# AFE_mezzanine.net
KiCad netlist of a schematic drawn in Altium Designer
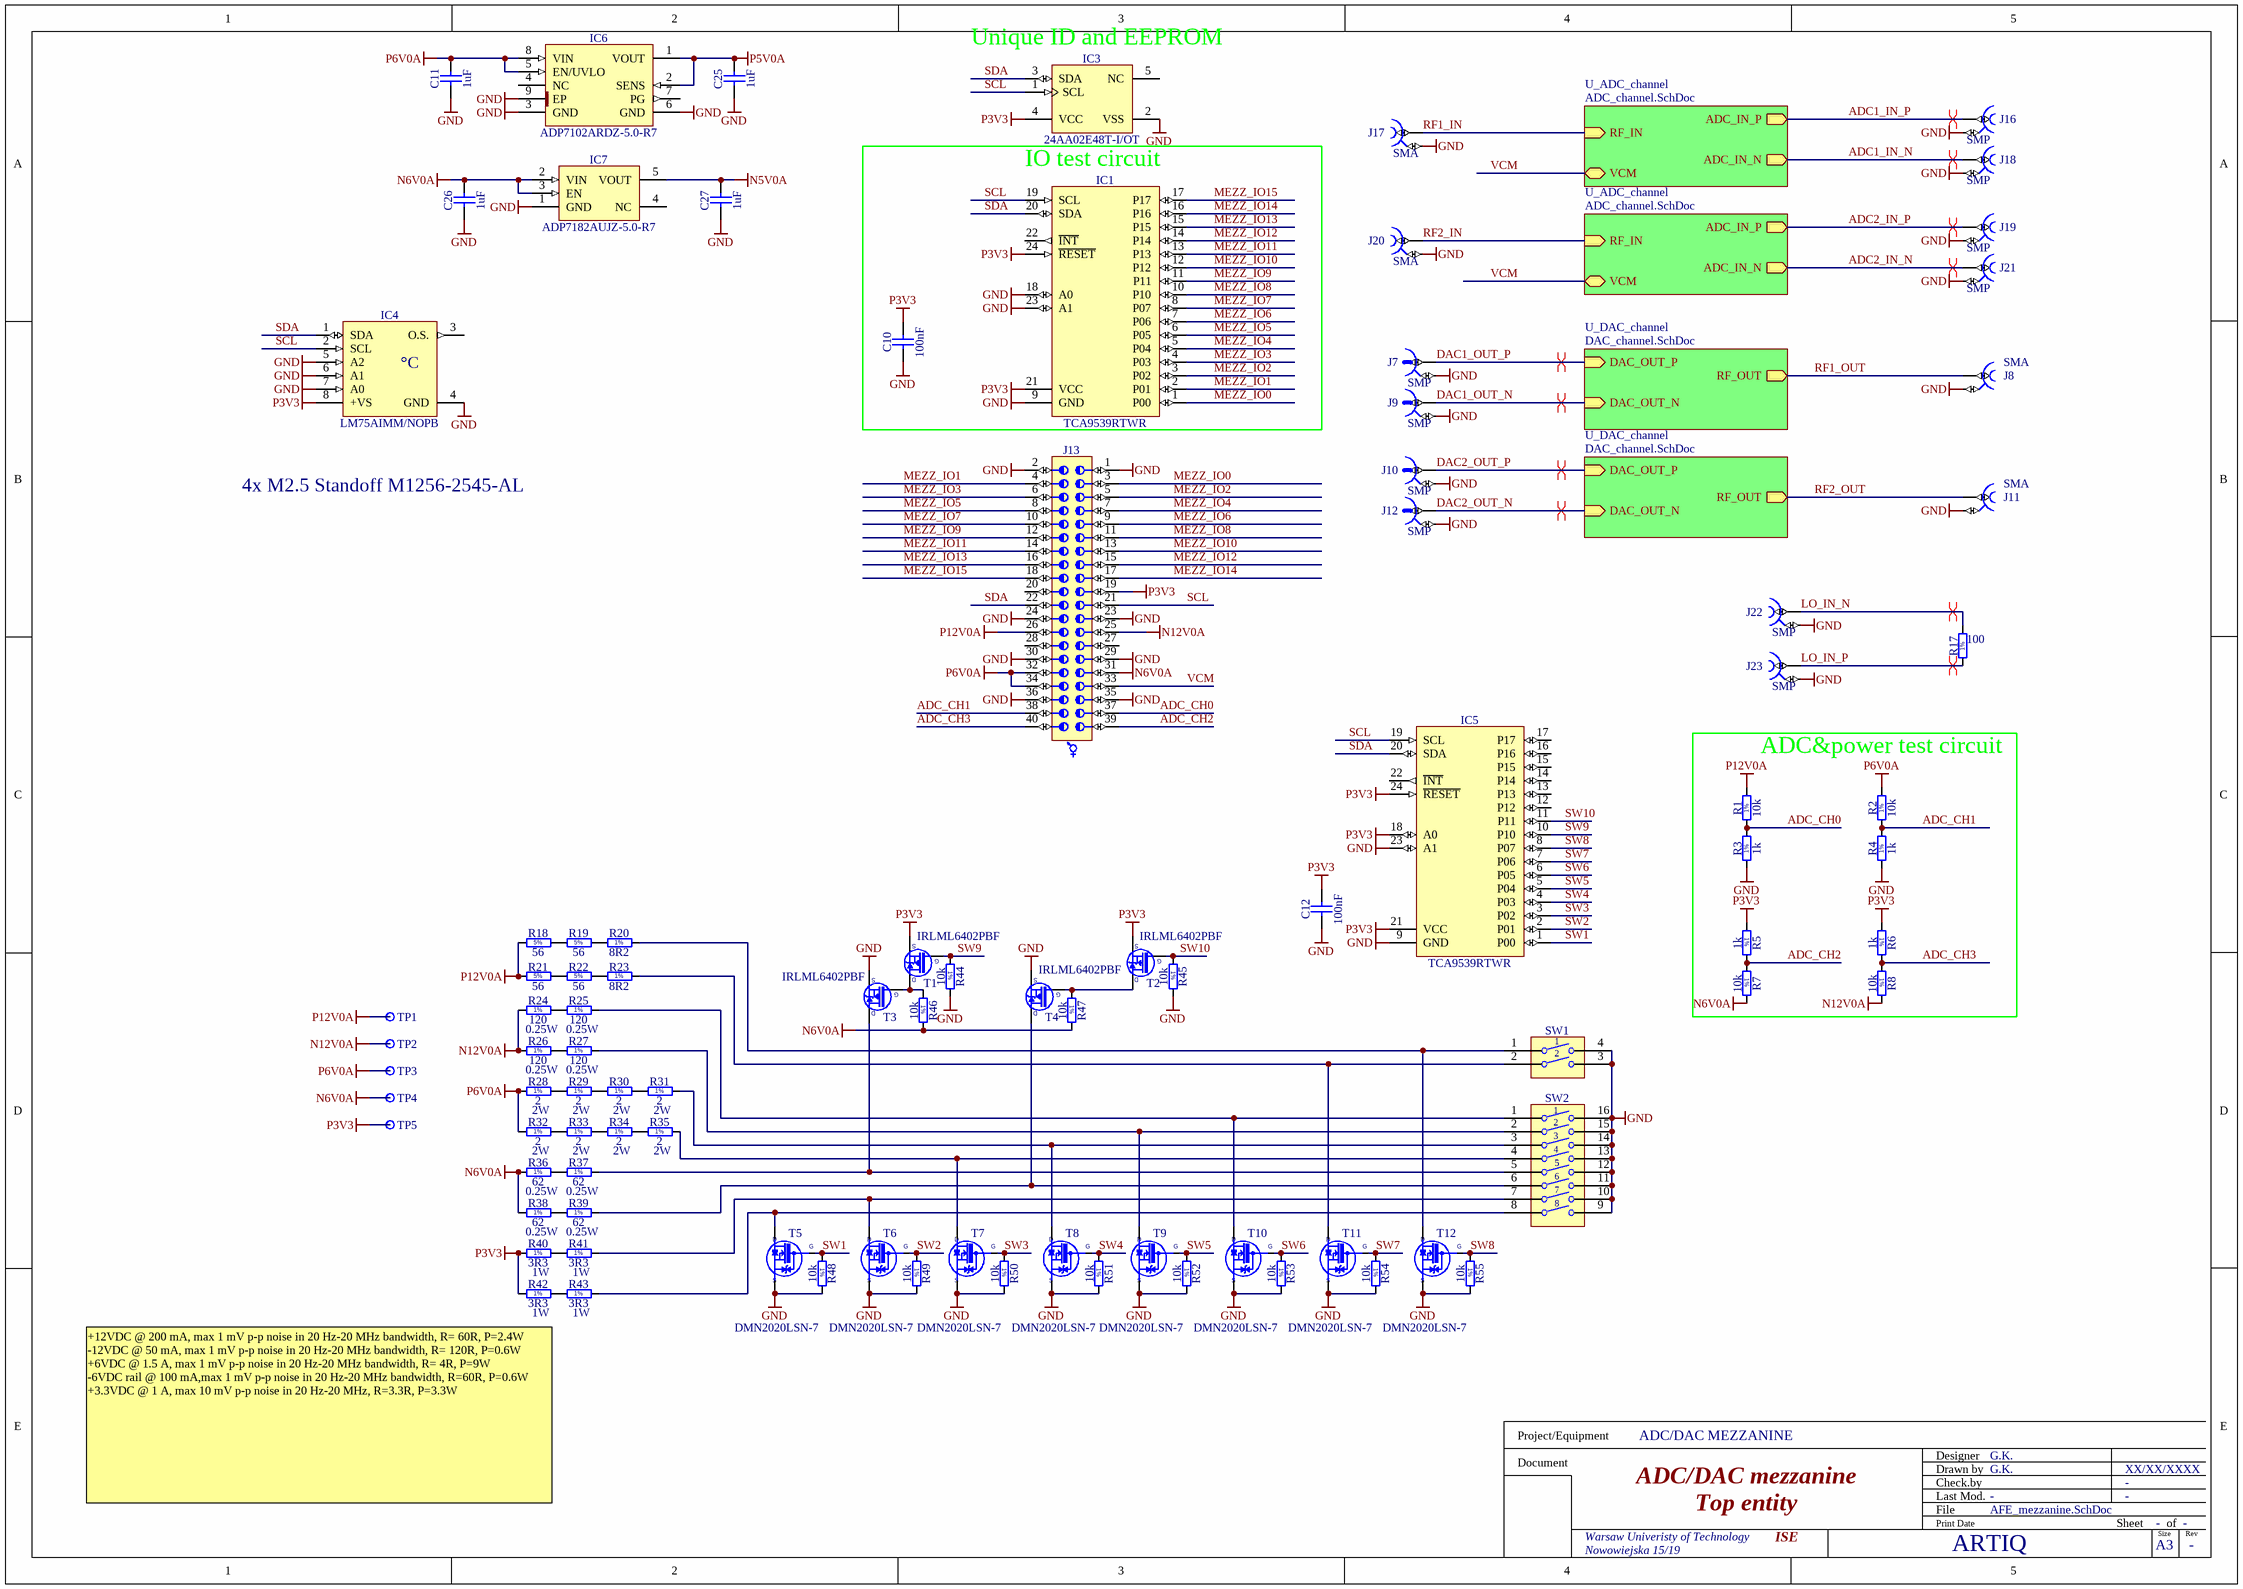
[diagram p0: AFE_mezzanine.SchDoc]

(export (version "E")
  (design (tool "Eeschema 10.0.6"))
  (components
    (comp (ref "C10")
      (value "100nF")
      (footprint "CAPC1005X55N")
      (description "Non-polarised capacitor")
      (fields
        (field (name "PART NUMBER") "CC0402_100NF_16V_10%_X5R")
        (field (name "VOLTAGE") "16V")
        (field (name "AUTHOR") "CERN DEM JLC")
      )
      (libsource (lib "Capacitors") (part "Capacitor - non polarized"))
    )
    (comp (ref "C11")
      (value "1uF")
      (footprint "CAPC2012X140N")
      (description "Non-polarised capacitor")
      (fields
        (field (name "PART NUMBER") "CC0805_1UF_35V_20%_X7R")
        (field (name "VOLTAGE") "35V")
        (field (name "AUTHOR") "CERN DEM JLC")
      )
      (libsource (lib "Capacitors") (part "Capacitor - non polarized"))
    )
    (comp (ref "C12")
      (value "100nF")
      (footprint "CAPC1005X55N")
      (description "Non-polarised capacitor")
      (fields
        (field (name "PART NUMBER") "CC0402_100NF_16V_10%_X5R")
        (field (name "VOLTAGE") "16V")
        (field (name "AUTHOR") "CERN DEM JLC")
      )
      (libsource (lib "Capacitors") (part "Capacitor - non polarized"))
    )
    (comp (ref "C25")
      (value "1uF")
      (footprint "CAPC2012X140N")
      (description "Non-polarised capacitor")
      (fields
        (field (name "PART NUMBER") "CC0805_1UF_35V_20%_X7R")
        (field (name "VOLTAGE") "35V")
        (field (name "AUTHOR") "CERN DEM JLC")
      )
      (libsource (lib "Capacitors") (part "Capacitor - non polarized"))
    )
    (comp (ref "C26")
      (value "1uF")
      (footprint "CAPC2012X140N")
      (description "Non-polarised capacitor")
      (fields
        (field (name "PART NUMBER") "CC0805_1UF_35V_20%_X7R")
        (field (name "VOLTAGE") "35V")
        (field (name "AUTHOR") "CERN DEM JLC")
      )
      (libsource (lib "Capacitors") (part "Capacitor - non polarized"))
    )
    (comp (ref "C27")
      (value "1uF")
      (footprint "CAPC2012X140N")
      (description "Non-polarised capacitor")
      (fields
        (field (name "PART NUMBER") "CC0805_1UF_35V_20%_X7R")
        (field (name "VOLTAGE") "35V")
        (field (name "AUTHOR") "CERN DEM JLC")
      )
      (libsource (lib "Capacitors") (part "Capacitor - non polarized"))
    )
    (comp (ref "IC1")
      (value "TCA9539RTWR")
      (footprint "QFN50P400X400X80-25N-S255")
      (description "Low-Voltage 16-Bit I2C and SMBus I/O Expander")
      (fields (field (name "MANUFACTURER") "TEXAS INSTRUMENTS") (field (name "AUTHOR") "CERN DEM MR"))
      (libsource (lib "ICs And Semiconductors") (part "TCA9539RTWR"))
    )
    (comp (ref "IC3")
      (value "24AA02E48T-I/OT")
      (footprint "SOT95P280X145-5N")
      (description "1.7V-5.5V, 2K I2C Serial EEPROM With EUI-48 Node Identity")
      (fields (field (name "MANUFACTURER") "MICROCHIP TECHNOLOGY") (field (name "AUTHOR") "CERN DEM MR"))
      (libsource (lib "ICs And Semiconductors") (part "24AA02E48T-I/OT"))
    )
    (comp (ref "IC4")
      (value "LM75AIMM/NOPB")
      (footprint "SOP65P490X109-8N")
      (description "Digital Temperature Sensor and Thermal Watchdog with Two-Wire Interface")
      (fields (field (name "MANUFACTURER") "TEXAS INSTRUMENTS") (field (name "AUTHOR") "CERN DEM JLC"))
      (libsource (lib "ICs And Semiconductors") (part "LM75"))
    )
    (comp (ref "IC5")
      (value "TCA9539RTWR")
      (footprint "QFN50P400X400X80-25N-S255")
      (description "Low-Voltage 16-Bit I2C and SMBus I/O Expander")
      (fields (field (name "MANUFACTURER") "TEXAS INSTRUMENTS") (field (name "AUTHOR") "CERN DEM MR"))
      (libsource (lib "ICs And Semiconductors") (part "TCA9539RTWR"))
    )
    (comp (ref "IC6")
      (value "ADP7102ARDZ-5.0-R7")
      (footprint "SOIC127P600X175-9N-R241X309")
      (description "300 mA, Low Noise, CMOS LDO Linear Regulator")
      (fields (field (name "MANUFACTURER") "ANALOG DEVICES") (field (name "AUTHOR") "CERN DEM JLC"))
      (libsource (lib "ICs And Semiconductors") (part "ADP7102ARDZ-X.X-R7"))
    )
    (comp (ref "IC7")
      (value "ADP7182AUJZ-5.0-R7")
      (footprint "SOT95P280X90-5N")
      (description "–5V, 200 mA, Low Noise, Linear Regulator")
      (fields (field (name "MANUFACTURER") "ANALOG DEVICES") (field (name "AUTHOR") "CERN DEM JLC"))
      (libsource (lib "ICs And Semiconductors") (part "ADP7182AUJZ-X.X-R7"))
    )
    (comp (ref "J7")
      (value "SMP")
      (footprint "MOLEX_85305-0232")
      (fields
        (field (name "PART NUMBER") "MOLEX_85305-0232")
        (field (name "MANUFACTURER") "MOLEX")
        (field (name "MANUFACTURER PART NUMBER") "85305-0232")
        (field (name "AUTHOR") "CERN DEM JMW")
      )
      (libsource (lib "Connectors") (part "Coax_1Male_1Shield"))
    )
    (comp (ref "J8")
      (value "SMA")
      (footprint "TELEGARTNER_J01151A0451")
      (fields
        (field (name "PART NUMBER") "TELEGARTNER_J01151A0451")
        (field (name "MANUFACTURER") "TELEGARTNER")
        (field (name "MANUFACTURER PART NUMBER") "J01151A0451")
        (field (name "AUTHOR") "CERN DEM JLC")
      )
      (libsource (lib "") (part "Coax_1Female_1Shield_1"))
    )
    (comp (ref "J9")
      (value "SMP")
      (footprint "MOLEX_85305-0232")
      (fields
        (field (name "PART NUMBER") "MOLEX_85305-0232")
        (field (name "MANUFACTURER") "MOLEX")
        (field (name "MANUFACTURER PART NUMBER") "85305-0232")
        (field (name "AUTHOR") "CERN DEM JMW")
      )
      (libsource (lib "Connectors") (part "Coax_1Male_1Shield"))
    )
    (comp (ref "J10")
      (value "SMP")
      (footprint "MOLEX_85305-0232")
      (fields
        (field (name "PART NUMBER") "MOLEX_85305-0232")
        (field (name "MANUFACTURER") "MOLEX")
        (field (name "MANUFACTURER PART NUMBER") "85305-0232")
        (field (name "AUTHOR") "CERN DEM JMW")
      )
      (libsource (lib "Connectors") (part "Coax_1Male_1Shield"))
    )
    (comp (ref "J11")
      (value "SMA")
      (footprint "TELEGARTNER_J01151A0451")
      (fields
        (field (name "PART NUMBER") "TELEGARTNER_J01151A0451")
        (field (name "MANUFACTURER") "TELEGARTNER")
        (field (name "MANUFACTURER PART NUMBER") "J01151A0451")
        (field (name "AUTHOR") "CERN DEM JLC")
      )
      (libsource (lib "") (part "Coax_1Female_1Shield_1"))
    )
    (comp (ref "J12")
      (value "SMP")
      (footprint "MOLEX_85305-0232")
      (fields
        (field (name "PART NUMBER") "MOLEX_85305-0232")
        (field (name "MANUFACTURER") "MOLEX")
        (field (name "MANUFACTURER PART NUMBER") "85305-0232")
        (field (name "AUTHOR") "CERN DEM JMW")
      )
      (libsource (lib "Connectors") (part "Coax_1Male_1Shield"))
    )
    (comp (ref "J13")
      (value "~")
      (footprint "SAMTEC_LSS-120-03-L-DV-A")
      (description "Connector 40 Hermaphroditic")
      (fields
        (field (name "PART NUMBER") "SAMTEC_LSS-120-03-L-DV-A")
        (field (name "MANUFACTURER") "SAMTEC")
        (field (name "AUTHOR") "CERN DEM JMW")
      )
      (libsource (lib "Connectors") (part "Connector 40 Hermaphroditic"))
    )
    (comp (ref "J16")
      (value "SMP")
      (footprint "AMPHENOL_SMP-MSLD-PCT-10")
      (fields
        (field (name "PART NUMBER") "AMPHENOL_SMP-MSLD-PCT-10")
        (field (name "MANUFACTURER") "AMPHENOL")
        (field (name "MANUFACTURER PART NUMBER") "SMP-MSLD-PCT-10")
        (field (name "AUTHOR") "CERN DEM JLC")
      )
      (libsource (lib "") (part "Coax_1Female_1Shield_1"))
    )
    (comp (ref "J17")
      (value "SMA")
      (footprint "TELEGARTNER_J01151A0921")
      (fields
        (field (name "PART NUMBER") "TELEGARTNER_J01151A0921")
        (field (name "MANUFACTURER") "TELEGARTNER")
        (field (name "MANUFACTURER PART NUMBER") "J01151A0921")
        (field (name "AUTHOR") "CERN DEM JLC")
      )
      (libsource (lib "Connectors") (part "Coax_1Female_1Shield"))
    )
    (comp (ref "J18")
      (value "SMP")
      (footprint "AMPHENOL_SMP-MSLD-PCT-10")
      (fields
        (field (name "PART NUMBER") "AMPHENOL_SMP-MSLD-PCT-10")
        (field (name "MANUFACTURER") "AMPHENOL")
        (field (name "MANUFACTURER PART NUMBER") "SMP-MSLD-PCT-10")
        (field (name "AUTHOR") "CERN DEM JLC")
      )
      (libsource (lib "") (part "Coax_1Female_1Shield_1"))
    )
    (comp (ref "J19")
      (value "SMP")
      (footprint "AMPHENOL_SMP-MSLD-PCT-10")
      (fields
        (field (name "PART NUMBER") "AMPHENOL_SMP-MSLD-PCT-10")
        (field (name "MANUFACTURER") "AMPHENOL")
        (field (name "MANUFACTURER PART NUMBER") "SMP-MSLD-PCT-10")
        (field (name "AUTHOR") "CERN DEM JLC")
      )
      (libsource (lib "") (part "Coax_1Female_1Shield_1"))
    )
    (comp (ref "J20")
      (value "SMA")
      (footprint "TELEGARTNER_J01151A0921")
      (fields
        (field (name "PART NUMBER") "TELEGARTNER_J01151A0921")
        (field (name "MANUFACTURER") "TELEGARTNER")
        (field (name "MANUFACTURER PART NUMBER") "J01151A0921")
        (field (name "AUTHOR") "CERN DEM JLC")
      )
      (libsource (lib "Connectors") (part "Coax_1Female_1Shield"))
    )
    (comp (ref "J21")
      (value "SMP")
      (footprint "AMPHENOL_SMP-MSLD-PCT-10")
      (fields
        (field (name "PART NUMBER") "AMPHENOL_SMP-MSLD-PCT-10")
        (field (name "MANUFACTURER") "AMPHENOL")
        (field (name "MANUFACTURER PART NUMBER") "SMP-MSLD-PCT-10")
        (field (name "AUTHOR") "CERN DEM JLC")
      )
      (libsource (lib "") (part "Coax_1Female_1Shield_1"))
    )
    (comp (ref "J22")
      (value "SMP")
      (footprint "AMPHENOL_SMP-MSLD-PCT-10")
      (fields
        (field (name "PART NUMBER") "AMPHENOL_SMP-MSLD-PCT-10")
        (field (name "MANUFACTURER") "AMPHENOL")
        (field (name "MANUFACTURER PART NUMBER") "SMP-MSLD-PCT-10")
        (field (name "AUTHOR") "CERN DEM JLC")
      )
      (libsource (lib "Connectors") (part "Coax_1Female_1Shield"))
    )
    (comp (ref "J23")
      (value "SMP")
      (footprint "AMPHENOL_SMP-MSLD-PCT-10")
      (fields
        (field (name "PART NUMBER") "AMPHENOL_SMP-MSLD-PCT-10")
        (field (name "MANUFACTURER") "AMPHENOL")
        (field (name "MANUFACTURER PART NUMBER") "SMP-MSLD-PCT-10")
        (field (name "AUTHOR") "CERN DEM JLC")
      )
      (libsource (lib "Connectors") (part "Coax_1Female_1Shield"))
    )
    (comp (ref "R1")
      (value "10k")
      (footprint "RESC1005X40N")
      (description "Resistor - 1%")
      (fields
        (field (name "PART NUMBER") "R0402_10K_1%_0.0625W_100PPM")
        (field (name "POWER") "0.0625W")
        (field (name "AUTHOR") "CERN DEM JLC")
      )
      (libsource (lib "Resistors") (part "Resistor - 1%"))
    )
    (comp (ref "R2")
      (value "10k")
      (footprint "RESC1005X40N")
      (description "Resistor - 1%")
      (fields
        (field (name "PART NUMBER") "R0402_10K_1%_0.0625W_100PPM")
        (field (name "POWER") "0.0625W")
        (field (name "AUTHOR") "CERN DEM JLC")
      )
      (libsource (lib "Resistors") (part "Resistor - 1%"))
    )
    (comp (ref "R3")
      (value "1k")
      (footprint "RESC1005X40N")
      (description "Resistor - 1%")
      (fields
        (field (name "PART NUMBER") "R0402_1K_1%_0.0625W_100PPM")
        (field (name "POWER") "0.0625W")
        (field (name "AUTHOR") "CERN DEM JLC")
      )
      (libsource (lib "Resistors") (part "Resistor - 1%"))
    )
    (comp (ref "R4")
      (value "1k")
      (footprint "RESC1005X40N")
      (description "Resistor - 1%")
      (fields
        (field (name "PART NUMBER") "R0402_1K_1%_0.0625W_100PPM")
        (field (name "POWER") "0.0625W")
        (field (name "AUTHOR") "CERN DEM JLC")
      )
      (libsource (lib "Resistors") (part "Resistor - 1%"))
    )
    (comp (ref "R5")
      (value "1k")
      (footprint "RESC1005X40N")
      (description "Resistor - 1%")
      (fields
        (field (name "PART NUMBER") "R0402_1K_1%_0.0625W_100PPM")
        (field (name "POWER") "0.0625W")
        (field (name "AUTHOR") "CERN DEM JLC")
      )
      (libsource (lib "Resistors") (part "Resistor - 1%"))
    )
    (comp (ref "R6")
      (value "1k")
      (footprint "RESC1005X40N")
      (description "Resistor - 1%")
      (fields
        (field (name "PART NUMBER") "R0402_1K_1%_0.0625W_100PPM")
        (field (name "POWER") "0.0625W")
        (field (name "AUTHOR") "CERN DEM JLC")
      )
      (libsource (lib "Resistors") (part "Resistor - 1%"))
    )
    (comp (ref "R7")
      (value "10k")
      (footprint "RESC1005X40N")
      (description "Resistor - 1%")
      (fields
        (field (name "PART NUMBER") "R0402_10K_1%_0.0625W_100PPM")
        (field (name "POWER") "0.0625W")
        (field (name "AUTHOR") "CERN DEM JLC")
      )
      (libsource (lib "Resistors") (part "Resistor - 1%"))
    )
    (comp (ref "R8")
      (value "10k")
      (footprint "RESC1005X40N")
      (description "Resistor - 1%")
      (fields
        (field (name "PART NUMBER") "R0402_10K_1%_0.0625W_100PPM")
        (field (name "POWER") "0.0625W")
        (field (name "AUTHOR") "CERN DEM JLC")
      )
      (libsource (lib "Resistors") (part "Resistor - 1%"))
    )
    (comp (ref "R17")
      (value "100")
      (footprint "RESC1005X40N")
      (description "Resistor - 1%")
      (fields
        (field (name "PART NUMBER") "R0402_100R_1%_0.0625W_100PPM")
        (field (name "POWER") "0.0625W")
        (field (name "AUTHOR") "CERN DEM JLC")
      )
      (libsource (lib "Resistors") (part "Resistor - 1%"))
    )
    (comp (ref "R18")
      (value "56")
      (footprint "RESC6331X70N")
      (description "Resistor - 5%")
      (fields
        (field (name "PART NUMBER") "R2512_56R_5%_1W_200PPM")
        (field (name "POWER") "1W")
        (field (name "AUTHOR") "CERN DEM JLC")
      )
      (libsource (lib "Resistors") (part "Resistor - 5%"))
    )
    (comp (ref "R19")
      (value "56")
      (footprint "RESC6331X70N")
      (description "Resistor - 5%")
      (fields
        (field (name "PART NUMBER") "R2512_56R_5%_1W_200PPM")
        (field (name "POWER") "1W")
        (field (name "AUTHOR") "CERN DEM JLC")
      )
      (libsource (lib "Resistors") (part "Resistor - 5%"))
    )
    (comp (ref "R20")
      (value "8R2")
      (footprint "RESC3216X65N")
      (description "Resistor - 1%")
      (fields
        (field (name "PART NUMBER") "R1206_8R2_1%_0.25W_200PPM")
        (field (name "POWER") "0.25W")
        (field (name "AUTHOR") "CERN DEM JLC")
      )
      (libsource (lib "Resistors") (part "Resistor - 1%"))
    )
    (comp (ref "R21")
      (value "56")
      (footprint "RESC6331X70N")
      (description "Resistor - 5%")
      (fields
        (field (name "PART NUMBER") "R2512_56R_5%_1W_200PPM")
        (field (name "POWER") "1W")
        (field (name "AUTHOR") "CERN DEM JLC")
      )
      (libsource (lib "Resistors") (part "Resistor - 5%"))
    )
    (comp (ref "R22")
      (value "56")
      (footprint "RESC6331X70N")
      (description "Resistor - 5%")
      (fields
        (field (name "PART NUMBER") "R2512_56R_5%_1W_200PPM")
        (field (name "POWER") "1W")
        (field (name "AUTHOR") "CERN DEM JLC")
      )
      (libsource (lib "Resistors") (part "Resistor - 5%"))
    )
    (comp (ref "R23")
      (value "8R2")
      (footprint "RESC3216X65N")
      (description "Resistor - 1%")
      (fields
        (field (name "PART NUMBER") "R1206_8R2_1%_0.25W_200PPM")
        (field (name "POWER") "0.25W")
        (field (name "AUTHOR") "CERN DEM JLC")
      )
      (libsource (lib "Resistors") (part "Resistor - 1%"))
    )
    (comp (ref "R24")
      (value "120")
      (footprint "RESC3216X65N")
      (description "Resistor - 1%")
      (fields
        (field (name "PART NUMBER") "R1206_120R_1%_0.25W_100PPM")
        (field (name "POWER") "0.25W")
        (field (name "TOLERANCE") "±1%")
        (field (name "AUTHOR") "CERN DEM JLC")
      )
      (libsource (lib "Resistors") (part "Resistor - 1%"))
    )
    (comp (ref "R25")
      (value "120")
      (footprint "RESC3216X65N")
      (description "Resistor - 1%")
      (fields
        (field (name "PART NUMBER") "R1206_120R_1%_0.25W_100PPM")
        (field (name "POWER") "0.25W")
        (field (name "TOLERANCE") "±1%")
        (field (name "AUTHOR") "CERN DEM JLC")
      )
      (libsource (lib "Resistors") (part "Resistor - 1%"))
    )
    (comp (ref "R26")
      (value "120")
      (footprint "RESC3216X65N")
      (description "Resistor - 1%")
      (fields
        (field (name "PART NUMBER") "R1206_120R_1%_0.25W_100PPM")
        (field (name "POWER") "0.25W")
        (field (name "TOLERANCE") "±1%")
        (field (name "AUTHOR") "CERN DEM JLC")
      )
      (libsource (lib "Resistors") (part "Resistor - 1%"))
    )
    (comp (ref "R27")
      (value "120")
      (footprint "RESC3216X65N")
      (description "Resistor - 1%")
      (fields
        (field (name "PART NUMBER") "R1206_120R_1%_0.25W_100PPM")
        (field (name "POWER") "0.25W")
        (field (name "TOLERANCE") "±1%")
        (field (name "AUTHOR") "CERN DEM JLC")
      )
      (libsource (lib "Resistors") (part "Resistor - 1%"))
    )
    (comp (ref "R28")
      (value "2")
      (footprint "RESM11670X449N")
      (description "Resistor - 1%")
      (fields
        (field (name "PART NUMBER") "R4527_2R_1%_2W_50PPM")
        (field (name "POWER") "2W")
        (field (name "TOLERANCE") "±1%")
        (field (name "AUTHOR") "CERN DEM JLC")
      )
      (libsource (lib "Resistors") (part "Resistor - 1%"))
    )
    (comp (ref "R29")
      (value "2")
      (footprint "RESM11670X449N")
      (description "Resistor - 1%")
      (fields
        (field (name "PART NUMBER") "R4527_2R_1%_2W_50PPM")
        (field (name "POWER") "2W")
        (field (name "TOLERANCE") "±1%")
        (field (name "AUTHOR") "CERN DEM JLC")
      )
      (libsource (lib "Resistors") (part "Resistor - 1%"))
    )
    (comp (ref "R30")
      (value "2")
      (footprint "RESM11670X449N")
      (description "Resistor - 1%")
      (fields
        (field (name "PART NUMBER") "R4527_2R_1%_2W_50PPM")
        (field (name "POWER") "2W")
        (field (name "TOLERANCE") "±1%")
        (field (name "AUTHOR") "CERN DEM JLC")
      )
      (libsource (lib "Resistors") (part "Resistor - 1%"))
    )
    (comp (ref "R31")
      (value "2")
      (footprint "RESM11670X449N")
      (description "Resistor - 1%")
      (fields
        (field (name "PART NUMBER") "R4527_2R_1%_2W_50PPM")
        (field (name "POWER") "2W")
        (field (name "TOLERANCE") "±1%")
        (field (name "AUTHOR") "CERN DEM JLC")
      )
      (libsource (lib "Resistors") (part "Resistor - 1%"))
    )
    (comp (ref "R32")
      (value "2")
      (footprint "RESM11670X449N")
      (description "Resistor - 1%")
      (fields
        (field (name "PART NUMBER") "R4527_2R_1%_2W_50PPM")
        (field (name "POWER") "2W")
        (field (name "TOLERANCE") "±1%")
        (field (name "AUTHOR") "CERN DEM JLC")
      )
      (libsource (lib "Resistors") (part "Resistor - 1%"))
    )
    (comp (ref "R33")
      (value "2")
      (footprint "RESM11670X449N")
      (description "Resistor - 1%")
      (fields
        (field (name "PART NUMBER") "R4527_2R_1%_2W_50PPM")
        (field (name "POWER") "2W")
        (field (name "TOLERANCE") "±1%")
        (field (name "AUTHOR") "CERN DEM JLC")
      )
      (libsource (lib "Resistors") (part "Resistor - 1%"))
    )
    (comp (ref "R34")
      (value "2")
      (footprint "RESM11670X449N")
      (description "Resistor - 1%")
      (fields
        (field (name "PART NUMBER") "R4527_2R_1%_2W_50PPM")
        (field (name "POWER") "2W")
        (field (name "TOLERANCE") "±1%")
        (field (name "AUTHOR") "CERN DEM JLC")
      )
      (libsource (lib "Resistors") (part "Resistor - 1%"))
    )
    (comp (ref "R35")
      (value "2")
      (footprint "RESM11670X449N")
      (description "Resistor - 1%")
      (fields
        (field (name "PART NUMBER") "R4527_2R_1%_2W_50PPM")
        (field (name "POWER") "2W")
        (field (name "TOLERANCE") "±1%")
        (field (name "AUTHOR") "CERN DEM JLC")
      )
      (libsource (lib "Resistors") (part "Resistor - 1%"))
    )
    (comp (ref "R36")
      (value "62")
      (footprint "RESC3216X65N")
      (description "Resistor - 1%")
      (fields
        (field (name "PART NUMBER") "R1206_62R_1%_0.25W_100PPM")
        (field (name "POWER") "0.25W")
        (field (name "TOLERANCE") "±1%")
        (field (name "AUTHOR") "CERN DEM JLC")
      )
      (libsource (lib "Resistors") (part "Resistor - 1%"))
    )
    (comp (ref "R37")
      (value "62")
      (footprint "RESC3216X65N")
      (description "Resistor - 1%")
      (fields
        (field (name "PART NUMBER") "R1206_62R_1%_0.25W_100PPM")
        (field (name "POWER") "0.25W")
        (field (name "TOLERANCE") "±1%")
        (field (name "AUTHOR") "CERN DEM JLC")
      )
      (libsource (lib "Resistors") (part "Resistor - 1%"))
    )
    (comp (ref "R38")
      (value "62")
      (footprint "RESC3216X65N")
      (description "Resistor - 1%")
      (fields
        (field (name "PART NUMBER") "R1206_62R_1%_0.25W_100PPM")
        (field (name "POWER") "0.25W")
        (field (name "TOLERANCE") "±1%")
        (field (name "AUTHOR") "CERN DEM JLC")
      )
      (libsource (lib "Resistors") (part "Resistor - 1%"))
    )
    (comp (ref "R39")
      (value "62")
      (footprint "RESC3216X65N")
      (description "Resistor - 1%")
      (fields
        (field (name "PART NUMBER") "R1206_62R_1%_0.25W_100PPM")
        (field (name "POWER") "0.25W")
        (field (name "TOLERANCE") "±1%")
        (field (name "AUTHOR") "CERN DEM JLC")
      )
      (libsource (lib "Resistors") (part "Resistor - 1%"))
    )
    (comp (ref "R40")
      (value "3R3")
      (footprint "RESC6331X70N")
      (description "Resistor - 1%")
      (fields
        (field (name "PART NUMBER") "R2512_3R3_1%_1W_200PPM")
        (field (name "POWER") "1W")
        (field (name "TOLERANCE") "±1%")
        (field (name "AUTHOR") "CERN DEM JLC")
      )
      (libsource (lib "Resistors") (part "Resistor - 1%"))
    )
    (comp (ref "R41")
      (value "3R3")
      (footprint "RESC6331X70N")
      (description "Resistor - 1%")
      (fields
        (field (name "PART NUMBER") "R2512_3R3_1%_1W_200PPM")
        (field (name "POWER") "1W")
        (field (name "TOLERANCE") "±1%")
        (field (name "AUTHOR") "CERN DEM JLC")
      )
      (libsource (lib "Resistors") (part "Resistor - 1%"))
    )
    (comp (ref "R42")
      (value "3R3")
      (footprint "RESC6331X70N")
      (description "Resistor - 1%")
      (fields
        (field (name "PART NUMBER") "R2512_3R3_1%_1W_200PPM")
        (field (name "POWER") "1W")
        (field (name "TOLERANCE") "±1%")
        (field (name "AUTHOR") "CERN DEM JLC")
      )
      (libsource (lib "Resistors") (part "Resistor - 1%"))
    )
    (comp (ref "R43")
      (value "3R3")
      (footprint "RESC6331X70N")
      (description "Resistor - 1%")
      (fields
        (field (name "PART NUMBER") "R2512_3R3_1%_1W_200PPM")
        (field (name "POWER") "1W")
        (field (name "TOLERANCE") "±1%")
        (field (name "AUTHOR") "CERN DEM JLC")
      )
      (libsource (lib "Resistors") (part "Resistor - 1%"))
    )
    (comp (ref "R44")
      (value "10k")
      (footprint "RESC1005X40N")
      (description "Resistor - 1%")
      (fields
        (field (name "PART NUMBER") "R0402_10K_1%_0.0625W_100PPM")
        (field (name "POWER") "0.0625W")
        (field (name "AUTHOR") "CERN DEM JLC")
      )
      (libsource (lib "Resistors") (part "Resistor - 1%"))
    )
    (comp (ref "R45")
      (value "10k")
      (footprint "RESC1005X40N")
      (description "Resistor - 1%")
      (fields
        (field (name "PART NUMBER") "R0402_10K_1%_0.0625W_100PPM")
        (field (name "POWER") "0.0625W")
        (field (name "AUTHOR") "CERN DEM JLC")
      )
      (libsource (lib "Resistors") (part "Resistor - 1%"))
    )
    (comp (ref "R46")
      (value "10k")
      (footprint "RESC1005X40N")
      (description "Resistor - 1%")
      (fields
        (field (name "PART NUMBER") "R0402_10K_1%_0.0625W_100PPM")
        (field (name "POWER") "0.0625W")
        (field (name "AUTHOR") "CERN DEM JLC")
      )
      (libsource (lib "Resistors") (part "Resistor - 1%"))
    )
    (comp (ref "R47")
      (value "10k")
      (footprint "RESC1005X40N")
      (description "Resistor - 1%")
      (fields
        (field (name "PART NUMBER") "R0402_10K_1%_0.0625W_100PPM")
        (field (name "POWER") "0.0625W")
        (field (name "AUTHOR") "CERN DEM JLC")
      )
      (libsource (lib "Resistors") (part "Resistor - 1%"))
    )
    (comp (ref "R48")
      (value "10k")
      (footprint "RESC1005X40N")
      (description "Resistor - 1%")
      (fields
        (field (name "PART NUMBER") "R0402_10K_1%_0.0625W_100PPM")
        (field (name "POWER") "0.0625W")
        (field (name "AUTHOR") "CERN DEM JLC")
      )
      (libsource (lib "Resistors") (part "Resistor - 1%"))
    )
    (comp (ref "R49")
      (value "10k")
      (footprint "RESC1005X40N")
      (description "Resistor - 1%")
      (fields
        (field (name "PART NUMBER") "R0402_10K_1%_0.0625W_100PPM")
        (field (name "POWER") "0.0625W")
        (field (name "AUTHOR") "CERN DEM JLC")
      )
      (libsource (lib "Resistors") (part "Resistor - 1%"))
    )
    (comp (ref "R50")
      (value "10k")
      (footprint "RESC1005X40N")
      (description "Resistor - 1%")
      (fields
        (field (name "PART NUMBER") "R0402_10K_1%_0.0625W_100PPM")
        (field (name "POWER") "0.0625W")
        (field (name "AUTHOR") "CERN DEM JLC")
      )
      (libsource (lib "Resistors") (part "Resistor - 1%"))
    )
    (comp (ref "R51")
      (value "10k")
      (footprint "RESC1005X40N")
      (description "Resistor - 1%")
      (fields
        (field (name "PART NUMBER") "R0402_10K_1%_0.0625W_100PPM")
        (field (name "POWER") "0.0625W")
        (field (name "AUTHOR") "CERN DEM JLC")
      )
      (libsource (lib "Resistors") (part "Resistor - 1%"))
    )
    (comp (ref "R52")
      (value "10k")
      (footprint "RESC1005X40N")
      (description "Resistor - 1%")
      (fields
        (field (name "PART NUMBER") "R0402_10K_1%_0.0625W_100PPM")
        (field (name "POWER") "0.0625W")
        (field (name "AUTHOR") "CERN DEM JLC")
      )
      (libsource (lib "Resistors") (part "Resistor - 1%"))
    )
    (comp (ref "R53")
      (value "10k")
      (footprint "RESC1005X40N")
      (description "Resistor - 1%")
      (fields
        (field (name "PART NUMBER") "R0402_10K_1%_0.0625W_100PPM")
        (field (name "POWER") "0.0625W")
        (field (name "AUTHOR") "CERN DEM JLC")
      )
      (libsource (lib "Resistors") (part "Resistor - 1%"))
    )
    (comp (ref "R54")
      (value "10k")
      (footprint "RESC1005X40N")
      (description "Resistor - 1%")
      (fields
        (field (name "PART NUMBER") "R0402_10K_1%_0.0625W_100PPM")
        (field (name "POWER") "0.0625W")
        (field (name "AUTHOR") "CERN DEM JLC")
      )
      (libsource (lib "Resistors") (part "Resistor - 1%"))
    )
    (comp (ref "R55")
      (value "10k")
      (footprint "RESC1005X40N")
      (description "Resistor - 1%")
      (fields
        (field (name "PART NUMBER") "R0402_10K_1%_0.0625W_100PPM")
        (field (name "POWER") "0.0625W")
        (field (name "AUTHOR") "CERN DEM JLC")
      )
      (libsource (lib "Resistors") (part "Resistor - 1%"))
    )
    (comp (ref "SW1")
      (value "Switch")
      (footprint "SW_OMRON_A6S-2102-H")
      (description "2 Ways SPST DIP Switch")
      (fields
        (field (name "PART NUMBER") "SW_OMRON_A6S-2102-H")
        (field (name "MANUFACTURER") "OMRON")
        (field (name "AUTHOR") "CERN DEM JMW")
      )
      (libsource (lib "Eletro-mechanical") (part "SW 2x SPST DIP Switch"))
    )
    (comp (ref "SW2")
      (value "Switch")
      (footprint "SW_OMRON_A6S-8102-H")
      (description "8 Ways SPST DIP Switch")
      (fields
        (field (name "PART NUMBER") "SW_OMRON_A6S-8102-H")
        (field (name "MANUFACTURER") "OMRON")
        (field (name "AUTHOR") "CERN DEM JMW")
      )
      (libsource (lib "Eletro-mechanical") (part "SW 8x SPST DIP Switch"))
    )
    (comp (ref "T1")
      (value "IRLML6402PBF")
      (footprint "SOT95P237X112-3N")
      (description "P-CHANNEL MOSFET WITH ZENER DIODE")
      (fields (field (name "MANUFACTURER") "INTERNATIONAL RECTIFIER") (field (name "AUTHOR") "CERN DEM JLC"))
      (libsource (lib "ICs And Semiconductors") (part "P-MOSFET-DZ 1G 2S 3D"))
    )
    (comp (ref "T2")
      (value "IRLML6402PBF")
      (footprint "SOT95P237X112-3N")
      (description "P-CHANNEL MOSFET WITH ZENER DIODE")
      (fields (field (name "MANUFACTURER") "INTERNATIONAL RECTIFIER") (field (name "AUTHOR") "CERN DEM JLC"))
      (libsource (lib "ICs And Semiconductors") (part "P-MOSFET-DZ 1G 2S 3D"))
    )
    (comp (ref "T3")
      (value "IRLML6402PBF")
      (footprint "SOT95P237X112-3N")
      (description "P-CHANNEL MOSFET WITH ZENER DIODE")
      (fields (field (name "MANUFACTURER") "INTERNATIONAL RECTIFIER") (field (name "AUTHOR") "CERN DEM JLC"))
      (libsource (lib "ICs And Semiconductors") (part "P-MOSFET-DZ 1G 2S 3D"))
    )
    (comp (ref "T4")
      (value "IRLML6402PBF")
      (footprint "SOT95P237X112-3N")
      (description "P-CHANNEL MOSFET WITH ZENER DIODE")
      (fields (field (name "MANUFACTURER") "INTERNATIONAL RECTIFIER") (field (name "AUTHOR") "CERN DEM JLC"))
      (libsource (lib "ICs And Semiconductors") (part "P-MOSFET-DZ 1G 2S 3D"))
    )
    (comp (ref "T5")
      (value "DMN2020LSN-7")
      (footprint "SOT95P285X140-3N")
      (description "20V, 6.9A, N-Channel Enhancement Mode MOSFET")
      (fields (field (name "MANUFACTURER") "DIODES INCORPORATED") (field (name "AUTHOR") "CERN DEM JLC"))
      (libsource (lib "ICs And Semiconductors") (part "DMN2020LSN-7"))
    )
    (comp (ref "T6")
      (value "DMN2020LSN-7")
      (footprint "SOT95P285X140-3N")
      (description "20V, 6.9A, N-Channel Enhancement Mode MOSFET")
      (fields (field (name "MANUFACTURER") "DIODES INCORPORATED") (field (name "AUTHOR") "CERN DEM JLC"))
      (libsource (lib "ICs And Semiconductors") (part "DMN2020LSN-7"))
    )
    (comp (ref "T7")
      (value "DMN2020LSN-7")
      (footprint "SOT95P285X140-3N")
      (description "20V, 6.9A, N-Channel Enhancement Mode MOSFET")
      (fields (field (name "MANUFACTURER") "DIODES INCORPORATED") (field (name "AUTHOR") "CERN DEM JLC"))
      (libsource (lib "ICs And Semiconductors") (part "DMN2020LSN-7"))
    )
    (comp (ref "T8")
      (value "DMN2020LSN-7")
      (footprint "SOT95P285X140-3N")
      (description "20V, 6.9A, N-Channel Enhancement Mode MOSFET")
      (fields (field (name "MANUFACTURER") "DIODES INCORPORATED") (field (name "AUTHOR") "CERN DEM JLC"))
      (libsource (lib "ICs And Semiconductors") (part "DMN2020LSN-7"))
    )
    (comp (ref "T9")
      (value "DMN2020LSN-7")
      (footprint "SOT95P285X140-3N")
      (description "20V, 6.9A, N-Channel Enhancement Mode MOSFET")
      (fields (field (name "MANUFACTURER") "DIODES INCORPORATED") (field (name "AUTHOR") "CERN DEM JLC"))
      (libsource (lib "ICs And Semiconductors") (part "DMN2020LSN-7"))
    )
    (comp (ref "T10")
      (value "DMN2020LSN-7")
      (footprint "SOT95P285X140-3N")
      (description "20V, 6.9A, N-Channel Enhancement Mode MOSFET")
      (fields (field (name "MANUFACTURER") "DIODES INCORPORATED") (field (name "AUTHOR") "CERN DEM JLC"))
      (libsource (lib "ICs And Semiconductors") (part "DMN2020LSN-7"))
    )
    (comp (ref "T11")
      (value "DMN2020LSN-7")
      (footprint "SOT95P285X140-3N")
      (description "20V, 6.9A, N-Channel Enhancement Mode MOSFET")
      (fields (field (name "MANUFACTURER") "DIODES INCORPORATED") (field (name "AUTHOR") "CERN DEM JLC"))
      (libsource (lib "ICs And Semiconductors") (part "DMN2020LSN-7"))
    )
    (comp (ref "T12")
      (value "DMN2020LSN-7")
      (footprint "SOT95P285X140-3N")
      (description "20V, 6.9A, N-Channel Enhancement Mode MOSFET")
      (fields (field (name "MANUFACTURER") "DIODES INCORPORATED") (field (name "AUTHOR") "CERN DEM JLC"))
      (libsource (lib "ICs And Semiconductors") (part "DMN2020LSN-7"))
    )
    (comp (ref "TP1")
      (value "Test Point")
      (footprint "TPS127")
      (fields (field (name "PART NUMBER") "SMD_PAD_1.27X1.27MM") (field (name "AUTHOR") "CERN DEM JLC"))
      (libsource (lib "Eletro-mechanical") (part "Test Point"))
    )
    (comp (ref "TP2")
      (value "Test Point")
      (footprint "TPS127")
      (fields (field (name "PART NUMBER") "SMD_PAD_1.27X1.27MM") (field (name "AUTHOR") "CERN DEM JLC"))
      (libsource (lib "Eletro-mechanical") (part "Test Point"))
    )
    (comp (ref "TP3")
      (value "Test Point")
      (footprint "TPS127")
      (fields (field (name "PART NUMBER") "SMD_PAD_1.27X1.27MM") (field (name "AUTHOR") "CERN DEM JLC"))
      (libsource (lib "Eletro-mechanical") (part "Test Point"))
    )
    (comp (ref "TP4")
      (value "Test Point")
      (footprint "TPS127")
      (fields (field (name "PART NUMBER") "SMD_PAD_1.27X1.27MM") (field (name "AUTHOR") "CERN DEM JLC"))
      (libsource (lib "Eletro-mechanical") (part "Test Point"))
    )
    (comp (ref "TP5")
      (value "Test Point")
      (footprint "TPS127")
      (fields (field (name "PART NUMBER") "SMD_PAD_1.27X1.27MM") (field (name "AUTHOR") "CERN DEM JLC"))
      (libsource (lib "Eletro-mechanical") (part "Test Point"))
    )
  )
  (nets
    (net (code "1") (name "/ADC1_IN_N") (class "Default")
      (node (ref "J18") (pin "1") (pinfunction "1_1") (pintype "bidirectional"))
    )
    (net (code "2") (name "/ADC1_IN_P") (class "Default")
      (node (ref "J16") (pin "1") (pinfunction "1_1") (pintype "bidirectional"))
    )
    (net (code "3") (name "/ADC2_IN_N") (class "Default")
      (node (ref "J21") (pin "1") (pinfunction "1_1") (pintype "bidirectional"))
    )
    (net (code "4") (name "/ADC2_IN_P") (class "Default")
      (node (ref "J19") (pin "1") (pinfunction "1_1") (pintype "bidirectional"))
    )
    (net (code "5") (name "/ADC_CH0") (class "Default")
      (node (ref "J13") (pin "37") (pinfunction "37_37") (pintype "bidirectional"))
      (node (ref "R1") (pin "1") (pinfunction "1_1") (pintype "passive"))
      (node (ref "R3") (pin "2") (pinfunction "2_2") (pintype "passive"))
    )
    (net (code "6") (name "/ADC_CH1") (class "Default")
      (node (ref "J13") (pin "38") (pinfunction "38_38") (pintype "bidirectional"))
      (node (ref "R2") (pin "1") (pinfunction "1_1") (pintype "passive"))
      (node (ref "R4") (pin "2") (pinfunction "2_2") (pintype "passive"))
    )
    (net (code "7") (name "/ADC_CH2") (class "Default")
      (node (ref "J13") (pin "39") (pinfunction "39_39") (pintype "bidirectional"))
      (node (ref "R5") (pin "2") (pinfunction "2_2") (pintype "passive"))
      (node (ref "R7") (pin "1") (pinfunction "1_1") (pintype "passive"))
    )
    (net (code "8") (name "/ADC_CH3") (class "Default")
      (node (ref "J13") (pin "40") (pinfunction "40_40") (pintype "bidirectional"))
      (node (ref "R6") (pin "2") (pinfunction "2_2") (pintype "passive"))
      (node (ref "R8") (pin "1") (pinfunction "1_1") (pintype "passive"))
    )
    (net (code "9") (name "/DAC1_OUT_N") (class "Default")
      (node (ref "J9") (pin "1") (pinfunction "1_1") (pintype "bidirectional"))
    )
    (net (code "10") (name "/DAC1_OUT_P") (class "Default")
      (node (ref "J7") (pin "1") (pinfunction "1_1") (pintype "bidirectional"))
    )
    (net (code "11") (name "/DAC2_OUT_N") (class "Default")
      (node (ref "J12") (pin "1") (pinfunction "1_1") (pintype "bidirectional"))
    )
    (net (code "12") (name "/DAC2_OUT_P") (class "Default")
      (node (ref "J10") (pin "1") (pinfunction "1_1") (pintype "bidirectional"))
    )
    (net (code "13") (name "/LO_IN_N") (class "Default")
      (node (ref "J22") (pin "1") (pinfunction "1_1") (pintype "bidirectional"))
      (node (ref "R17") (pin "2") (pinfunction "2_2") (pintype "passive"))
    )
    (net (code "14") (name "/LO_IN_P") (class "Default")
      (node (ref "J23") (pin "1") (pinfunction "1_1") (pintype "bidirectional"))
      (node (ref "R17") (pin "1") (pinfunction "1_1") (pintype "passive"))
    )
    (net (code "15") (name "/MEZZ_IO0") (class "Default")
      (node (ref "IC1") (pin "1") (pinfunction "P00_1") (pintype "bidirectional"))
      (node (ref "J13") (pin "3") (pinfunction "3_3") (pintype "bidirectional"))
    )
    (net (code "16") (name "/MEZZ_IO1") (class "Default")
      (node (ref "IC1") (pin "2") (pinfunction "P01_2") (pintype "bidirectional"))
      (node (ref "J13") (pin "4") (pinfunction "4_4") (pintype "bidirectional"))
    )
    (net (code "17") (name "/MEZZ_IO2") (class "Default")
      (node (ref "IC1") (pin "3") (pinfunction "P02_3") (pintype "bidirectional"))
      (node (ref "J13") (pin "5") (pinfunction "5_5") (pintype "bidirectional"))
    )
    (net (code "18") (name "/MEZZ_IO3") (class "Default")
      (node (ref "IC1") (pin "4") (pinfunction "P03_4") (pintype "bidirectional"))
      (node (ref "J13") (pin "6") (pinfunction "6_6") (pintype "bidirectional"))
    )
    (net (code "19") (name "/MEZZ_IO4") (class "Default")
      (node (ref "IC1") (pin "5") (pinfunction "P04_5") (pintype "bidirectional"))
      (node (ref "J13") (pin "7") (pinfunction "7_7") (pintype "bidirectional"))
    )
    (net (code "20") (name "/MEZZ_IO5") (class "Default")
      (node (ref "IC1") (pin "6") (pinfunction "P05_6") (pintype "bidirectional"))
      (node (ref "J13") (pin "8") (pinfunction "8_8") (pintype "bidirectional"))
    )
    (net (code "21") (name "/MEZZ_IO6") (class "Default")
      (node (ref "IC1") (pin "7") (pinfunction "P06_7") (pintype "bidirectional"))
      (node (ref "J13") (pin "9") (pinfunction "9_9") (pintype "bidirectional"))
    )
    (net (code "22") (name "/MEZZ_IO7") (class "Default")
      (node (ref "IC1") (pin "8") (pinfunction "P07_8") (pintype "bidirectional"))
      (node (ref "J13") (pin "10") (pinfunction "10_10") (pintype "bidirectional"))
    )
    (net (code "23") (name "/MEZZ_IO8") (class "Default")
      (node (ref "IC1") (pin "10") (pinfunction "P10_10") (pintype "bidirectional"))
      (node (ref "J13") (pin "11") (pinfunction "11_11") (pintype "bidirectional"))
    )
    (net (code "24") (name "/MEZZ_IO9") (class "Default")
      (node (ref "IC1") (pin "11") (pinfunction "P11_11") (pintype "bidirectional"))
      (node (ref "J13") (pin "12") (pinfunction "12_12") (pintype "bidirectional"))
    )
    (net (code "25") (name "/MEZZ_IO10") (class "Default")
      (node (ref "IC1") (pin "12") (pinfunction "P12_12") (pintype "bidirectional"))
      (node (ref "J13") (pin "13") (pinfunction "13_13") (pintype "bidirectional"))
    )
    (net (code "26") (name "/MEZZ_IO11") (class "Default")
      (node (ref "IC1") (pin "13") (pinfunction "P13_13") (pintype "bidirectional"))
      (node (ref "J13") (pin "14") (pinfunction "14_14") (pintype "bidirectional"))
    )
    (net (code "27") (name "/MEZZ_IO12") (class "Default")
      (node (ref "IC1") (pin "14") (pinfunction "P14_14") (pintype "bidirectional"))
      (node (ref "J13") (pin "15") (pinfunction "15_15") (pintype "bidirectional"))
    )
    (net (code "28") (name "/MEZZ_IO13") (class "Default")
      (node (ref "IC1") (pin "15") (pinfunction "P15_15") (pintype "bidirectional"))
      (node (ref "J13") (pin "16") (pinfunction "16_16") (pintype "bidirectional"))
    )
    (net (code "29") (name "/MEZZ_IO14") (class "Default")
      (node (ref "IC1") (pin "16") (pinfunction "P16_16") (pintype "bidirectional"))
      (node (ref "J13") (pin "17") (pinfunction "17_17") (pintype "bidirectional"))
    )
    (net (code "30") (name "/MEZZ_IO15") (class "Default")
      (node (ref "IC1") (pin "17") (pinfunction "P17_17") (pintype "bidirectional"))
      (node (ref "J13") (pin "18") (pinfunction "18_18") (pintype "bidirectional"))
    )
    (net (code "31") (name "/RF1_IN") (class "Default")
      (node (ref "J17") (pin "1") (pinfunction "1_1") (pintype "bidirectional"))
    )
    (net (code "32") (name "/RF1_OUT") (class "Default")
      (node (ref "J8") (pin "1") (pinfunction "1_1") (pintype "bidirectional"))
    )
    (net (code "33") (name "/RF2_IN") (class "Default")
      (node (ref "J20") (pin "1") (pinfunction "1_1") (pintype "bidirectional"))
    )
    (net (code "34") (name "/RF2_OUT") (class "Default")
      (node (ref "J11") (pin "1") (pinfunction "1_1") (pintype "bidirectional"))
    )
    (net (code "35") (name "/SCL") (class "Default")
      (node (ref "IC1") (pin "19") (pinfunction "SCL_19") (pintype "input"))
      (node (ref "IC3") (pin "1") (pinfunction "SCL_1") (pintype "input"))
      (node (ref "IC4") (pin "2") (pinfunction "SCL_2") (pintype "input"))
      (node (ref "IC5") (pin "19") (pinfunction "SCL_19") (pintype "input"))
      (node (ref "J13") (pin "21") (pinfunction "21_21") (pintype "bidirectional"))
    )
    (net (code "36") (name "/SDA") (class "Default")
      (node (ref "IC1") (pin "20") (pinfunction "SDA_20") (pintype "bidirectional"))
      (node (ref "IC3") (pin "3") (pinfunction "SDA_3") (pintype "bidirectional"))
      (node (ref "IC4") (pin "1") (pinfunction "SDA_1") (pintype "bidirectional"))
      (node (ref "IC5") (pin "20") (pinfunction "SDA_20") (pintype "bidirectional"))
      (node (ref "J13") (pin "22") (pinfunction "22_22") (pintype "bidirectional"))
    )
    (net (code "37") (name "/SW1") (class "Default")
      (node (ref "IC5") (pin "1") (pinfunction "P00_1") (pintype "bidirectional"))
      (node (ref "R48") (pin "1") (pinfunction "1_1") (pintype "passive"))
      (node (ref "T5") (pin "1") (pinfunction "G_1") (pintype "passive"))
    )
    (net (code "38") (name "/SW2") (class "Default")
      (node (ref "IC5") (pin "2") (pinfunction "P01_2") (pintype "bidirectional"))
      (node (ref "R49") (pin "1") (pinfunction "1_1") (pintype "passive"))
      (node (ref "T6") (pin "1") (pinfunction "G_1") (pintype "passive"))
    )
    (net (code "39") (name "/SW3") (class "Default")
      (node (ref "IC5") (pin "3") (pinfunction "P02_3") (pintype "bidirectional"))
      (node (ref "R50") (pin "1") (pinfunction "1_1") (pintype "passive"))
      (node (ref "T7") (pin "1") (pinfunction "G_1") (pintype "passive"))
    )
    (net (code "40") (name "/SW4") (class "Default")
      (node (ref "IC5") (pin "4") (pinfunction "P03_4") (pintype "bidirectional"))
      (node (ref "R51") (pin "1") (pinfunction "1_1") (pintype "passive"))
      (node (ref "T8") (pin "1") (pinfunction "G_1") (pintype "passive"))
    )
    (net (code "41") (name "/SW5") (class "Default")
      (node (ref "IC5") (pin "5") (pinfunction "P04_5") (pintype "bidirectional"))
      (node (ref "R52") (pin "1") (pinfunction "1_1") (pintype "passive"))
      (node (ref "T9") (pin "1") (pinfunction "G_1") (pintype "passive"))
    )
    (net (code "42") (name "/SW6") (class "Default")
      (node (ref "IC5") (pin "6") (pinfunction "P05_6") (pintype "bidirectional"))
      (node (ref "R53") (pin "1") (pinfunction "1_1") (pintype "passive"))
      (node (ref "T10") (pin "1") (pinfunction "G_1") (pintype "passive"))
    )
    (net (code "43") (name "/SW7") (class "Default")
      (node (ref "IC5") (pin "7") (pinfunction "P06_7") (pintype "bidirectional"))
      (node (ref "R54") (pin "1") (pinfunction "1_1") (pintype "passive"))
      (node (ref "T11") (pin "1") (pinfunction "G_1") (pintype "passive"))
    )
    (net (code "44") (name "/SW8") (class "Default")
      (node (ref "IC5") (pin "8") (pinfunction "P07_8") (pintype "bidirectional"))
      (node (ref "R55") (pin "1") (pinfunction "1_1") (pintype "passive"))
      (node (ref "T12") (pin "1") (pinfunction "G_1") (pintype "passive"))
    )
    (net (code "45") (name "/SW9") (class "Default")
      (node (ref "IC5") (pin "10") (pinfunction "P10_10") (pintype "bidirectional"))
      (node (ref "R44") (pin "1") (pinfunction "1_1") (pintype "passive"))
      (node (ref "T1") (pin "1") (pinfunction "G_1") (pintype "passive"))
    )
    (net (code "46") (name "/SW10") (class "Default")
      (node (ref "IC5") (pin "11") (pinfunction "P11_11") (pintype "bidirectional"))
      (node (ref "R45") (pin "1") (pinfunction "1_1") (pintype "passive"))
      (node (ref "T2") (pin "1") (pinfunction "G_1") (pintype "passive"))
    )
    (net (code "47") (name "/VCM") (class "Default")
      (node (ref "J13") (pin "33") (pinfunction "33_33") (pintype "bidirectional"))
    )
    (net (code "48") (name "GND") (class "Default")
      (node (ref "C10") (pin "1") (pinfunction "1_1") (pintype "passive"))
      (node (ref "C11") (pin "1") (pinfunction "1_1") (pintype "passive"))
      (node (ref "C12") (pin "1") (pinfunction "1_1") (pintype "passive"))
      (node (ref "C25") (pin "1") (pinfunction "1_1") (pintype "passive"))
      (node (ref "C26") (pin "1") (pinfunction "1_1") (pintype "passive"))
      (node (ref "C27") (pin "1") (pinfunction "1_1") (pintype "passive"))
      (node (ref "IC1") (pin "18") (pinfunction "A0_18") (pintype "bidirectional"))
      (node (ref "IC1") (pin "23") (pinfunction "A1_23") (pintype "bidirectional"))
      (node (ref "IC1") (pin "9") (pinfunction "GND_9") (pintype "power_in"))
      (node (ref "IC3") (pin "2") (pinfunction "VSS_2") (pintype "power_in"))
      (node (ref "IC4") (pin "4") (pinfunction "GND_4") (pintype "power_in"))
      (node (ref "IC4") (pin "5") (pinfunction "A2_5") (pintype "input"))
      (node (ref "IC4") (pin "6") (pinfunction "A1_6") (pintype "input"))
      (node (ref "IC4") (pin "7") (pinfunction "A0_7") (pintype "input"))
      (node (ref "IC5") (pin "23") (pinfunction "A1_23") (pintype "bidirectional"))
      (node (ref "IC5") (pin "9") (pinfunction "GND_9") (pintype "power_in"))
      (node (ref "IC6") (pin "3") (pinfunction "GND_3") (pintype "power_in"))
      (node (ref "IC6") (pin "6") (pinfunction "GND_6") (pintype "power_in"))
      (node (ref "IC6") (pin "9") (pinfunction "EP_9") (pintype "power_in"))
      (node (ref "IC7") (pin "1") (pinfunction "GND_1") (pintype "power_in"))
      (node (ref "J10") (pin "2") (pinfunction "2_2") (pintype "bidirectional"))
      (node (ref "J11") (pin "2") (pinfunction "2_2") (pintype "bidirectional"))
      (node (ref "J12") (pin "2") (pinfunction "2_2") (pintype "bidirectional"))
      (node (ref "J13") (pin "1") (pinfunction "1_1") (pintype "bidirectional"))
      (node (ref "J13") (pin "2") (pinfunction "2_2") (pintype "bidirectional"))
      (node (ref "J13") (pin "23") (pinfunction "23_23") (pintype "bidirectional"))
      (node (ref "J13") (pin "24") (pinfunction "24_24") (pintype "bidirectional"))
      (node (ref "J13") (pin "29") (pinfunction "29_29") (pintype "bidirectional"))
      (node (ref "J13") (pin "30") (pinfunction "30_30") (pintype "bidirectional"))
      (node (ref "J13") (pin "35") (pinfunction "35_35") (pintype "bidirectional"))
      (node (ref "J13") (pin "36") (pinfunction "36_36") (pintype "bidirectional"))
      (node (ref "J16") (pin "2") (pinfunction "2_2") (pintype "bidirectional"))
      (node (ref "J17") (pin "2") (pinfunction "2_2") (pintype "bidirectional"))
      (node (ref "J18") (pin "2") (pinfunction "2_2") (pintype "bidirectional"))
      (node (ref "J19") (pin "2") (pinfunction "2_2") (pintype "bidirectional"))
      (node (ref "J20") (pin "2") (pinfunction "2_2") (pintype "bidirectional"))
      (node (ref "J21") (pin "2") (pinfunction "2_2") (pintype "bidirectional"))
      (node (ref "J22") (pin "2") (pinfunction "2_2") (pintype "bidirectional"))
      (node (ref "J23") (pin "2") (pinfunction "2_2") (pintype "bidirectional"))
      (node (ref "J7") (pin "2") (pinfunction "2_2") (pintype "bidirectional"))
      (node (ref "J8") (pin "2") (pinfunction "2_2") (pintype "bidirectional"))
      (node (ref "J9") (pin "2") (pinfunction "2_2") (pintype "bidirectional"))
      (node (ref "R3") (pin "1") (pinfunction "1_1") (pintype "passive"))
      (node (ref "R4") (pin "1") (pinfunction "1_1") (pintype "passive"))
      (node (ref "R44") (pin "2") (pinfunction "2_2") (pintype "passive"))
      (node (ref "R45") (pin "2") (pinfunction "2_2") (pintype "passive"))
      (node (ref "R48") (pin "2") (pinfunction "2_2") (pintype "passive"))
      (node (ref "R49") (pin "2") (pinfunction "2_2") (pintype "passive"))
      (node (ref "R50") (pin "2") (pinfunction "2_2") (pintype "passive"))
      (node (ref "R51") (pin "2") (pinfunction "2_2") (pintype "passive"))
      (node (ref "R52") (pin "2") (pinfunction "2_2") (pintype "passive"))
      (node (ref "R53") (pin "2") (pinfunction "2_2") (pintype "passive"))
      (node (ref "R54") (pin "2") (pinfunction "2_2") (pintype "passive"))
      (node (ref "R55") (pin "2") (pinfunction "2_2") (pintype "passive"))
      (node (ref "SW1") (pin "3") (pinfunction "3_3") (pintype "passive"))
      (node (ref "SW1") (pin "4") (pinfunction "4_4") (pintype "passive"))
      (node (ref "SW2") (pin "10") (pinfunction "10_10") (pintype "passive"))
      (node (ref "SW2") (pin "11") (pinfunction "11_11") (pintype "passive"))
      (node (ref "SW2") (pin "12") (pinfunction "12_12") (pintype "passive"))
      (node (ref "SW2") (pin "13") (pinfunction "13_13") (pintype "passive"))
      (node (ref "SW2") (pin "14") (pinfunction "14_14") (pintype "passive"))
      (node (ref "SW2") (pin "15") (pinfunction "15_15") (pintype "passive"))
      (node (ref "SW2") (pin "16") (pinfunction "16_16") (pintype "passive"))
      (node (ref "SW2") (pin "9") (pinfunction "9_9") (pintype "passive"))
      (node (ref "T10") (pin "2") (pinfunction "S_2") (pintype "passive"))
      (node (ref "T11") (pin "2") (pinfunction "S_2") (pintype "passive"))
      (node (ref "T12") (pin "2") (pinfunction "S_2") (pintype "passive"))
      (node (ref "T3") (pin "2") (pinfunction "S_2") (pintype "passive"))
      (node (ref "T4") (pin "2") (pinfunction "S_2") (pintype "passive"))
      (node (ref "T5") (pin "2") (pinfunction "S_2") (pintype "passive"))
      (node (ref "T6") (pin "2") (pinfunction "S_2") (pintype "passive"))
      (node (ref "T7") (pin "2") (pinfunction "S_2") (pintype "passive"))
      (node (ref "T8") (pin "2") (pinfunction "S_2") (pintype "passive"))
      (node (ref "T9") (pin "2") (pinfunction "S_2") (pintype "passive"))
    )
    (net (code "49") (name "N5V0A") (class "Default")
      (node (ref "C27") (pin "2") (pinfunction "2_2") (pintype "passive"))
      (node (ref "IC7") (pin "5") (pinfunction "VOUT_5") (pintype "power_in"))
    )
    (net (code "50") (name "N6V0A") (class "Default")
      (node (ref "C26") (pin "2") (pinfunction "2_2") (pintype "passive"))
      (node (ref "IC7") (pin "2") (pinfunction "VIN_2") (pintype "input"))
      (node (ref "IC7") (pin "3") (pinfunction "EN_3") (pintype "input"))
      (node (ref "J13") (pin "31") (pinfunction "31_31") (pintype "bidirectional"))
      (node (ref "R36") (pin "1") (pinfunction "1_1") (pintype "passive"))
      (node (ref "R38") (pin "1") (pinfunction "1_1") (pintype "passive"))
      (node (ref "R46") (pin "2") (pinfunction "2_2") (pintype "passive"))
      (node (ref "R47") (pin "2") (pinfunction "2_2") (pintype "passive"))
      (node (ref "R7") (pin "2") (pinfunction "2_2") (pintype "passive"))
      (node (ref "TP4") (pin "1") (pinfunction "1_1") (pintype "bidirectional"))
    )
    (net (code "51") (name "N12V0A") (class "Default")
      (node (ref "J13") (pin "25") (pinfunction "25_25") (pintype "bidirectional"))
      (node (ref "R24") (pin "1") (pinfunction "1_1") (pintype "passive"))
      (node (ref "R26") (pin "1") (pinfunction "1_1") (pintype "passive"))
      (node (ref "R8") (pin "2") (pinfunction "2_2") (pintype "passive"))
      (node (ref "TP2") (pin "1") (pinfunction "1_1") (pintype "bidirectional"))
    )
    (net (code "52") (name "Net-(R18-Pad2)") (class "Default")
      (node (ref "R18") (pin "2") (pinfunction "2_2") (pintype "passive"))
      (node (ref "R19") (pin "1") (pinfunction "1_1") (pintype "passive"))
    )
    (net (code "53") (name "Net-(R19-Pad2)") (class "Default")
      (node (ref "R19") (pin "2") (pinfunction "2_2") (pintype "passive"))
      (node (ref "R20") (pin "1") (pinfunction "1_1") (pintype "passive"))
    )
    (net (code "54") (name "Net-(R21-Pad2)") (class "Default")
      (node (ref "R21") (pin "2") (pinfunction "2_2") (pintype "passive"))
      (node (ref "R22") (pin "1") (pinfunction "1_1") (pintype "passive"))
    )
    (net (code "55") (name "Net-(R22-Pad2)") (class "Default")
      (node (ref "R22") (pin "2") (pinfunction "2_2") (pintype "passive"))
      (node (ref "R23") (pin "1") (pinfunction "1_1") (pintype "passive"))
    )
    (net (code "56") (name "Net-(R24-Pad2)") (class "Default")
      (node (ref "R24") (pin "2") (pinfunction "2_2") (pintype "passive"))
      (node (ref "R25") (pin "1") (pinfunction "1_1") (pintype "passive"))
    )
    (net (code "57") (name "Net-(R26-Pad2)") (class "Default")
      (node (ref "R26") (pin "2") (pinfunction "2_2") (pintype "passive"))
      (node (ref "R27") (pin "1") (pinfunction "1_1") (pintype "passive"))
    )
    (net (code "58") (name "Net-(R28-Pad2)") (class "Default")
      (node (ref "R28") (pin "2") (pinfunction "2_2") (pintype "passive"))
      (node (ref "R29") (pin "1") (pinfunction "1_1") (pintype "passive"))
    )
    (net (code "59") (name "Net-(R29-Pad2)") (class "Default")
      (node (ref "R29") (pin "2") (pinfunction "2_2") (pintype "passive"))
      (node (ref "R30") (pin "1") (pinfunction "1_1") (pintype "passive"))
    )
    (net (code "60") (name "Net-(R30-Pad2)") (class "Default")
      (node (ref "R30") (pin "2") (pinfunction "2_2") (pintype "passive"))
      (node (ref "R31") (pin "1") (pinfunction "1_1") (pintype "passive"))
    )
    (net (code "61") (name "Net-(R32-Pad2)") (class "Default")
      (node (ref "R32") (pin "2") (pinfunction "2_2") (pintype "passive"))
      (node (ref "R33") (pin "1") (pinfunction "1_1") (pintype "passive"))
    )
    (net (code "62") (name "Net-(R33-Pad2)") (class "Default")
      (node (ref "R33") (pin "2") (pinfunction "2_2") (pintype "passive"))
      (node (ref "R34") (pin "1") (pinfunction "1_1") (pintype "passive"))
    )
    (net (code "63") (name "Net-(R34-Pad2)") (class "Default")
      (node (ref "R34") (pin "2") (pinfunction "2_2") (pintype "passive"))
      (node (ref "R35") (pin "1") (pinfunction "1_1") (pintype "passive"))
    )
    (net (code "64") (name "Net-(R36-Pad2)") (class "Default")
      (node (ref "R36") (pin "2") (pinfunction "2_2") (pintype "passive"))
      (node (ref "R37") (pin "1") (pinfunction "1_1") (pintype "passive"))
    )
    (net (code "65") (name "Net-(R38-Pad2)") (class "Default")
      (node (ref "R38") (pin "2") (pinfunction "2_2") (pintype "passive"))
      (node (ref "R39") (pin "1") (pinfunction "1_1") (pintype "passive"))
    )
    (net (code "66") (name "Net-(R40-Pad2)") (class "Default")
      (node (ref "R40") (pin "2") (pinfunction "2_2") (pintype "passive"))
      (node (ref "R41") (pin "1") (pinfunction "1_1") (pintype "passive"))
    )
    (net (code "67") (name "Net-(R42-Pad2)") (class "Default")
      (node (ref "R42") (pin "2") (pinfunction "2_2") (pintype "passive"))
      (node (ref "R43") (pin "1") (pinfunction "1_1") (pintype "passive"))
    )
    (net (code "68") (name "Net-(T1-D)") (class "Default")
      (node (ref "R46") (pin "1") (pinfunction "1_1") (pintype "passive"))
      (node (ref "T1") (pin "3") (pinfunction "D_3") (pintype "passive"))
      (node (ref "T3") (pin "1") (pinfunction "G_1") (pintype "passive"))
    )
    (net (code "69") (name "Net-(T2-D)") (class "Default")
      (node (ref "R47") (pin "1") (pinfunction "1_1") (pintype "passive"))
      (node (ref "T2") (pin "3") (pinfunction "D_3") (pintype "passive"))
      (node (ref "T4") (pin "1") (pinfunction "G_1") (pintype "passive"))
    )
    (net (code "70") (name "Net-(T3-D)") (class "Default")
      (node (ref "R37") (pin "2") (pinfunction "2_2") (pintype "passive"))
      (node (ref "SW2") (pin "5") (pinfunction "5_5") (pintype "passive"))
      (node (ref "T3") (pin "3") (pinfunction "D_3") (pintype "passive"))
    )
    (net (code "71") (name "Net-(T4-D)") (class "Default")
      (node (ref "R39") (pin "2") (pinfunction "2_2") (pintype "passive"))
      (node (ref "SW2") (pin "6") (pinfunction "6_6") (pintype "passive"))
      (node (ref "T4") (pin "3") (pinfunction "D_3") (pintype "passive"))
    )
    (net (code "72") (name "Net-(T5-D)") (class "Default")
      (node (ref "R43") (pin "2") (pinfunction "2_2") (pintype "passive"))
      (node (ref "SW2") (pin "8") (pinfunction "8_8") (pintype "passive"))
      (node (ref "T5") (pin "3") (pinfunction "D_3") (pintype "passive"))
    )
    (net (code "73") (name "Net-(T6-D)") (class "Default")
      (node (ref "R41") (pin "2") (pinfunction "2_2") (pintype "passive"))
      (node (ref "SW2") (pin "7") (pinfunction "7_7") (pintype "passive"))
      (node (ref "T6") (pin "3") (pinfunction "D_3") (pintype "passive"))
    )
    (net (code "74") (name "Net-(T7-D)") (class "Default")
      (node (ref "R35") (pin "2") (pinfunction "2_2") (pintype "passive"))
      (node (ref "SW2") (pin "4") (pinfunction "4_4") (pintype "passive"))
      (node (ref "T7") (pin "3") (pinfunction "D_3") (pintype "passive"))
    )
    (net (code "75") (name "Net-(T8-D)") (class "Default")
      (node (ref "R31") (pin "2") (pinfunction "2_2") (pintype "passive"))
      (node (ref "SW2") (pin "3") (pinfunction "3_3") (pintype "passive"))
      (node (ref "T8") (pin "3") (pinfunction "D_3") (pintype "passive"))
    )
    (net (code "76") (name "Net-(T9-D)") (class "Default")
      (node (ref "R27") (pin "2") (pinfunction "2_2") (pintype "passive"))
      (node (ref "SW2") (pin "2") (pinfunction "2_2") (pintype "passive"))
      (node (ref "T9") (pin "3") (pinfunction "D_3") (pintype "passive"))
    )
    (net (code "77") (name "Net-(T10-D)") (class "Default")
      (node (ref "R25") (pin "2") (pinfunction "2_2") (pintype "passive"))
      (node (ref "SW2") (pin "1") (pinfunction "1_1") (pintype "passive"))
      (node (ref "T10") (pin "3") (pinfunction "D_3") (pintype "passive"))
    )
    (net (code "78") (name "Net-(T11-D)") (class "Default")
      (node (ref "R23") (pin "2") (pinfunction "2_2") (pintype "passive"))
      (node (ref "SW1") (pin "2") (pinfunction "2_2") (pintype "passive"))
      (node (ref "T11") (pin "3") (pinfunction "D_3") (pintype "passive"))
    )
    (net (code "79") (name "Net-(T12-D)") (class "Default")
      (node (ref "R20") (pin "2") (pinfunction "2_2") (pintype "passive"))
      (node (ref "SW1") (pin "1") (pinfunction "1_1") (pintype "passive"))
      (node (ref "T12") (pin "3") (pinfunction "D_3") (pintype "passive"))
    )
    (net (code "80") (name "P3V3") (class "Default")
      (node (ref "C10") (pin "2") (pinfunction "2_2") (pintype "passive"))
      (node (ref "C12") (pin "2") (pinfunction "2_2") (pintype "passive"))
      (node (ref "IC1") (pin "21") (pinfunction "VCC_21") (pintype "power_in"))
      (node (ref "IC1") (pin "24") (pinfunction "~{RESET}_24") (pintype "input"))
      (node (ref "IC3") (pin "4") (pinfunction "VCC_4") (pintype "power_in"))
      (node (ref "IC4") (pin "8") (pinfunction "+VS_8") (pintype "power_in"))
      (node (ref "IC5") (pin "18") (pinfunction "A0_18") (pintype "bidirectional"))
      (node (ref "IC5") (pin "21") (pinfunction "VCC_21") (pintype "power_in"))
      (node (ref "IC5") (pin "24") (pinfunction "~{RESET}_24") (pintype "input"))
      (node (ref "J13") (pin "19") (pinfunction "19_19") (pintype "bidirectional"))
      (node (ref "R40") (pin "1") (pinfunction "1_1") (pintype "passive"))
      (node (ref "R42") (pin "1") (pinfunction "1_1") (pintype "passive"))
      (node (ref "R5") (pin "1") (pinfunction "1_1") (pintype "passive"))
      (node (ref "R6") (pin "1") (pinfunction "1_1") (pintype "passive"))
      (node (ref "T1") (pin "2") (pinfunction "S_2") (pintype "passive"))
      (node (ref "T2") (pin "2") (pinfunction "S_2") (pintype "passive"))
      (node (ref "TP5") (pin "1") (pinfunction "1_1") (pintype "bidirectional"))
    )
    (net (code "81") (name "P5V0A") (class "Default")
      (node (ref "C25") (pin "2") (pinfunction "2_2") (pintype "passive"))
      (node (ref "IC6") (pin "1") (pinfunction "VOUT_1") (pintype "power_in"))
      (node (ref "IC6") (pin "2") (pinfunction "SENS_2") (pintype "input"))
    )
    (net (code "82") (name "P6V0A") (class "Default")
      (node (ref "C11") (pin "2") (pinfunction "2_2") (pintype "passive"))
      (node (ref "IC6") (pin "5") (pinfunction "EN/UVLO_5") (pintype "input"))
      (node (ref "IC6") (pin "8") (pinfunction "VIN_8") (pintype "input"))
      (node (ref "J13") (pin "32") (pinfunction "32_32") (pintype "bidirectional"))
      (node (ref "J13") (pin "34") (pinfunction "34_34") (pintype "bidirectional"))
      (node (ref "R2") (pin "2") (pinfunction "2_2") (pintype "passive"))
      (node (ref "R28") (pin "1") (pinfunction "1_1") (pintype "passive"))
      (node (ref "R32") (pin "1") (pinfunction "1_1") (pintype "passive"))
      (node (ref "TP3") (pin "1") (pinfunction "1_1") (pintype "bidirectional"))
    )
    (net (code "83") (name "P12V0A") (class "Default")
      (node (ref "J13") (pin "26") (pinfunction "26_26") (pintype "bidirectional"))
      (node (ref "R1") (pin "2") (pinfunction "2_2") (pintype "passive"))
      (node (ref "R18") (pin "1") (pinfunction "1_1") (pintype "passive"))
      (node (ref "R21") (pin "1") (pinfunction "1_1") (pintype "passive"))
      (node (ref "TP1") (pin "1") (pinfunction "1_1") (pintype "bidirectional"))
    )
    (net (code "84") (name "unconnected-(IC1-~{INT}-Pad22)") (class "Default")
      (node (ref "IC1") (pin "22") (pinfunction "~{INT}_22") (pintype "output"))
    )
    (net (code "85") (name "unconnected-(IC3-NC-Pad5)") (class "Default")
      (node (ref "IC3") (pin "5") (pinfunction "NC_5") (pintype "passive"))
    )
    (net (code "86") (name "unconnected-(IC4-O.S.-Pad3)") (class "Default")
      (node (ref "IC4") (pin "3") (pinfunction "O.S._3") (pintype "output"))
    )
    (net (code "87") (name "unconnected-(IC5-P12-Pad12)") (class "Default")
      (node (ref "IC5") (pin "12") (pinfunction "P12_12") (pintype "bidirectional"))
    )
    (net (code "88") (name "unconnected-(IC5-P13-Pad13)") (class "Default")
      (node (ref "IC5") (pin "13") (pinfunction "P13_13") (pintype "bidirectional"))
    )
    (net (code "89") (name "unconnected-(IC5-P14-Pad14)") (class "Default")
      (node (ref "IC5") (pin "14") (pinfunction "P14_14") (pintype "bidirectional"))
    )
    (net (code "90") (name "unconnected-(IC5-P15-Pad15)") (class "Default")
      (node (ref "IC5") (pin "15") (pinfunction "P15_15") (pintype "bidirectional"))
    )
    (net (code "91") (name "unconnected-(IC5-P16-Pad16)") (class "Default")
      (node (ref "IC5") (pin "16") (pinfunction "P16_16") (pintype "bidirectional"))
    )
    (net (code "92") (name "unconnected-(IC5-P17-Pad17)") (class "Default")
      (node (ref "IC5") (pin "17") (pinfunction "P17_17") (pintype "bidirectional"))
    )
    (net (code "93") (name "unconnected-(IC5-~{INT}-Pad22)") (class "Default")
      (node (ref "IC5") (pin "22") (pinfunction "~{INT}_22") (pintype "output"))
    )
    (net (code "94") (name "unconnected-(IC6-NC-Pad4)") (class "Default")
      (node (ref "IC6") (pin "4") (pinfunction "NC_4") (pintype "passive"))
    )
    (net (code "95") (name "unconnected-(IC6-PG-Pad7)") (class "Default")
      (node (ref "IC6") (pin "7") (pinfunction "PG_7") (pintype "output"))
    )
    (net (code "96") (name "unconnected-(IC7-NC-Pad4)") (class "Default")
      (node (ref "IC7") (pin "4") (pinfunction "NC_4") (pintype "passive"))
    )
    (net (code "97") (name "unconnected-(J13-Pad20)") (class "Default")
      (node (ref "J13") (pin "20") (pinfunction "20_20") (pintype "bidirectional"))
    )
    (net (code "98") (name "unconnected-(J13-Pad27)") (class "Default")
      (node (ref "J13") (pin "27") (pinfunction "27_27") (pintype "bidirectional"))
    )
    (net (code "99") (name "unconnected-(J13-Pad28)") (class "Default")
      (node (ref "J13") (pin "28") (pinfunction "28_28") (pintype "bidirectional"))
    )
  )
)
